# main.net
KiCad netlist of a schematic drawn in EAGLE
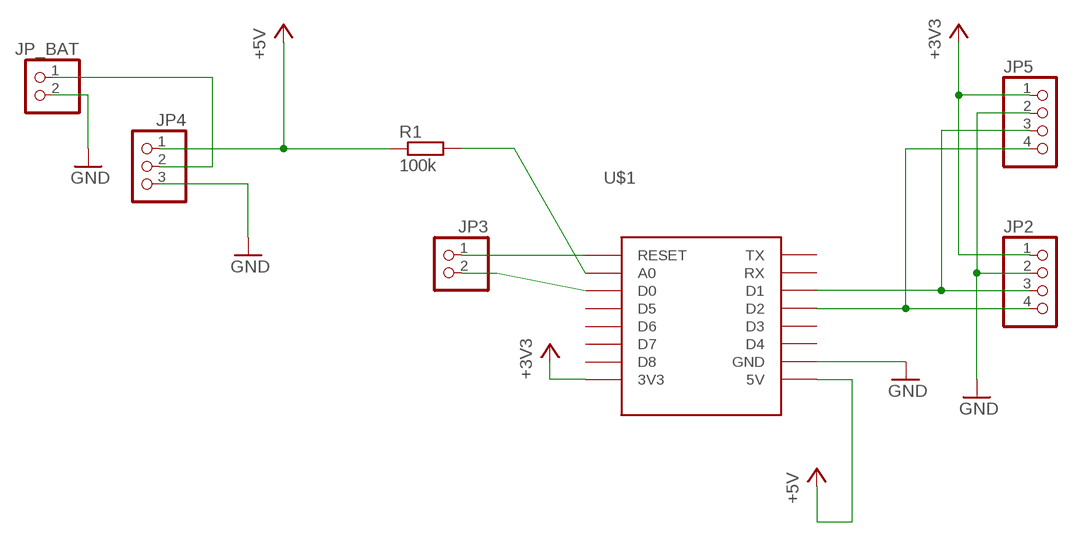
[diagram p0: schematic, sheet 1]

(export (version "E")
  (design (tool "Eeschema 10.0.6"))
  (components
    (comp (ref "JP2")
      (value "PINHD-1X4")
      (footprint "eagle-import:1X04")
      (libsource (lib "eagle-import") (part "PINHD-1X4"))
    )
    (comp (ref "JP3")
      (value "PINHD-1X2")
      (footprint "eagle-import:1X02")
      (libsource (lib "eagle-import") (part "PINHD-1X2"))
    )
    (comp (ref "JP4")
      (value "PINHD-1X3")
      (footprint "eagle-import:1X03")
      (libsource (lib "eagle-import") (part "PINHD-1X3"))
    )
    (comp (ref "JP5")
      (value "PINHD-1X4")
      (footprint "eagle-import:1X04")
      (libsource (lib "eagle-import") (part "PINHD-1X4"))
    )
    (comp (ref "JP_BAT")
      (value "PINHD-1X2")
      (footprint "eagle-import:1X02")
      (libsource (lib "eagle-import") (part "PINHD-1X2"))
    )
    (comp (ref "R1")
      (value "100k")
      (footprint "eagle-import:R0805")
      (libsource (lib "eagle-import") (part "R-EU_R0805"))
    )
    (comp (ref "U$1")
      (value "WEMOS-D1-MINI")
      (footprint "eagle-import:WEMOS-D1-MINI")
      (libsource (lib "eagle-import") (part "WEMOS-D1-MINI"))
    )
  )
  (nets
    (net (code "1") (name "+3V3") (class "Default")
      (node (ref "JP2") (pin "1") (pinfunction "1_1") (pintype "passive"))
      (node (ref "JP5") (pin "1") (pinfunction "1_1") (pintype "passive"))
      (node (ref "U$1") (pin "3V3") (pinfunction "3V3_3V3") (pintype "bidirectional"))
    )
    (net (code "2") (name "+5V") (class "Default")
      (node (ref "JP4") (pin "1") (pinfunction "1_1") (pintype "passive"))
      (node (ref "R1") (pin "1") (pinfunction "1_1") (pintype "passive"))
      (node (ref "U$1") (pin "5V") (pinfunction "5V_5V") (pintype "bidirectional"))
    )
    (net (code "3") (name "GND") (class "Default")
      (node (ref "JP2") (pin "2") (pinfunction "2_2") (pintype "passive"))
      (node (ref "JP4") (pin "3") (pinfunction "3_3") (pintype "passive"))
      (node (ref "JP5") (pin "2") (pinfunction "2_2") (pintype "passive"))
      (node (ref "JP_BAT") (pin "2") (pinfunction "2_2") (pintype "passive"))
      (node (ref "U$1") (pin "GND") (pinfunction "GND_GND") (pintype "bidirectional"))
    )
    (net (code "4") (name "Net-(JP2-Pad3)") (class "Default")
      (node (ref "JP2") (pin "3") (pinfunction "3_3") (pintype "passive"))
      (node (ref "JP5") (pin "3") (pinfunction "3_3") (pintype "passive"))
      (node (ref "U$1") (pin "D1") (pinfunction "D1_D1") (pintype "bidirectional"))
    )
    (net (code "5") (name "Net-(JP2-Pad4)") (class "Default")
      (node (ref "JP2") (pin "4") (pinfunction "4_4") (pintype "passive"))
      (node (ref "JP5") (pin "4") (pinfunction "4_4") (pintype "passive"))
      (node (ref "U$1") (pin "D2") (pinfunction "D2_D2") (pintype "bidirectional"))
    )
    (net (code "6") (name "Net-(JP3-Pad1)") (class "Default")
      (node (ref "JP3") (pin "1") (pinfunction "1_1") (pintype "passive"))
      (node (ref "U$1") (pin "RESET") (pinfunction "RESET_RESET") (pintype "bidirectional"))
    )
    (net (code "7") (name "Net-(JP3-Pad2)") (class "Default")
      (node (ref "JP3") (pin "2") (pinfunction "2_2") (pintype "passive"))
      (node (ref "U$1") (pin "D0") (pinfunction "D0_D0") (pintype "bidirectional"))
    )
    (net (code "8") (name "Net-(JP4-Pad2)") (class "Default")
      (node (ref "JP4") (pin "2") (pinfunction "2_2") (pintype "passive"))
      (node (ref "JP_BAT") (pin "1") (pinfunction "1_1") (pintype "passive"))
    )
    (net (code "9") (name "Net-(R1-Pad2)") (class "Default")
      (node (ref "R1") (pin "2") (pinfunction "2_2") (pintype "passive"))
      (node (ref "U$1") (pin "A0") (pinfunction "A0_A0") (pintype "bidirectional"))
    )
    (net (code "10") (name "unconnected-(U$1-PadD3)") (class "Default")
      (node (ref "U$1") (pin "D3") (pinfunction "D3_D3") (pintype "bidirectional"))
    )
    (net (code "11") (name "unconnected-(U$1-PadD4)") (class "Default")
      (node (ref "U$1") (pin "D4") (pinfunction "D4_D4") (pintype "bidirectional"))
    )
    (net (code "12") (name "unconnected-(U$1-PadD5)") (class "Default")
      (node (ref "U$1") (pin "D5") (pinfunction "D5_D5") (pintype "bidirectional"))
    )
    (net (code "13") (name "unconnected-(U$1-PadD6)") (class "Default")
      (node (ref "U$1") (pin "D6") (pinfunction "D6_D6") (pintype "bidirectional"))
    )
    (net (code "14") (name "unconnected-(U$1-PadD7)") (class "Default")
      (node (ref "U$1") (pin "D7") (pinfunction "D7_D7") (pintype "bidirectional"))
    )
    (net (code "15") (name "unconnected-(U$1-PadD8)") (class "Default")
      (node (ref "U$1") (pin "D8") (pinfunction "D8_D8") (pintype "bidirectional"))
    )
    (net (code "16") (name "unconnected-(U$1-PadRX)") (class "Default")
      (node (ref "U$1") (pin "RX") (pinfunction "RX_RX") (pintype "bidirectional"))
    )
    (net (code "17") (name "unconnected-(U$1-PadTX)") (class "Default")
      (node (ref "U$1") (pin "TX") (pinfunction "TX_TX") (pintype "bidirectional"))
    )
  )
)
